# Voltage_Sens.net
KiCad netlist of a schematic drawn in Altium Designer
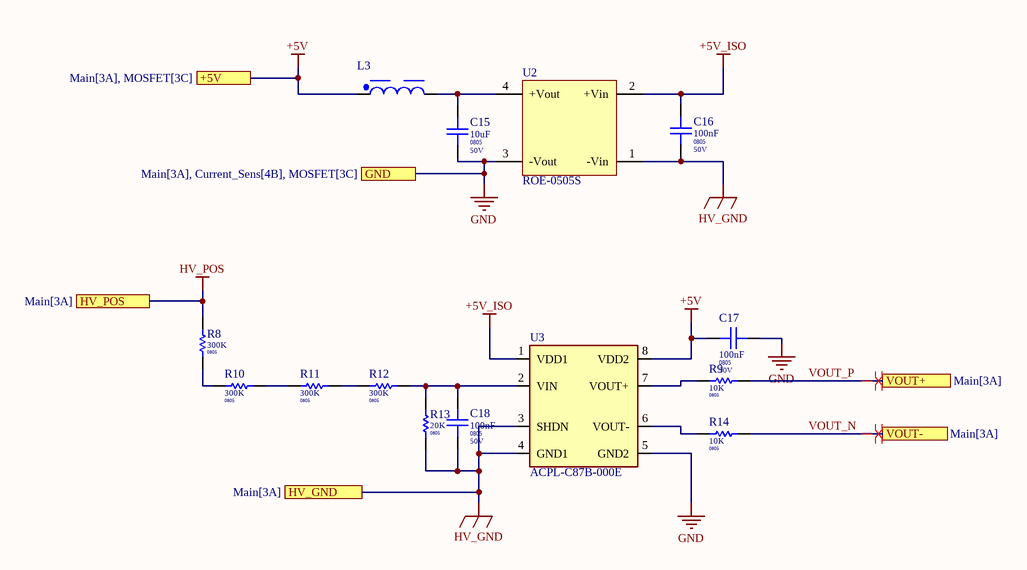
[diagram p0: Voltage_Sens.SchDoc]

(export (version "E")
  (design (tool "Eeschema 10.0.6"))
  (components
    (comp (ref "C15")
      (value "10uF")
      (footprint "CAPC 0805")
      (description "Capacitor Ceramic 10uF 50V 0805")
      (fields
        (field (name "TOLERANCE") "%10")
        (field (name "PACKAGE / CASE") "0805")
        (field (name "VOLTAGE") "50V")
        (field (name "PART NUMBER") "CAPC0588")
      )
      (libsource (lib "Aesk Database Library") (part "NPCapacitor"))
    )
    (comp (ref "C16")
      (value "100nF")
      (footprint "CAPC 0805")
      (description "Capacitor Ceramic 100nF 50V 0805")
      (fields
        (field (name "TOLERANCE") "%10")
        (field (name "PACKAGE / CASE") "0805")
        (field (name "VOLTAGE") "50V")
        (field (name "PART NUMBER") "CAPC0572")
      )
      (libsource (lib "Aesk Database Library") (part "NPCapacitor"))
    )
    (comp (ref "C17")
      (value "100nF")
      (footprint "CAPC 0805")
      (description "Capacitor Ceramic 100nF 50V 0805")
      (fields
        (field (name "TOLERANCE") "%10")
        (field (name "PACKAGE / CASE") "0805")
        (field (name "VOLTAGE") "50V")
        (field (name "PART NUMBER") "CAPC0572")
      )
      (libsource (lib "Aesk Database Library") (part "NPCapacitor"))
    )
    (comp (ref "C18")
      (value "100nF")
      (footprint "CAPC 0805")
      (description "Capacitor Ceramic 100nF 50V 0805")
      (fields
        (field (name "TOLERANCE") "%10")
        (field (name "PACKAGE / CASE") "0805")
        (field (name "VOLTAGE") "50V")
        (field (name "PART NUMBER") "CAPC0572")
      )
      (libsource (lib "Aesk Database Library") (part "NPCapacitor"))
    )
    (comp (ref "L3")
      (value "22uH, 0.66A")
      (footprint "WE-LQFS_3818")
      (description "WE-LQFS SMT Power Inductor, size 3818, 22uH, 0.66A, 481mOhm")
      (fields
        (field (name "MANUFACTURER PART NUMBER") "74406032220")
        (field (name "MANUFACTURER") "Wurth Elektronik")
      )
      (libsource (lib "WE - Passive Components") (part "Inductor - 2"))
    )
    (comp (ref "R8")
      (value "300K")
      (footprint "RESC 0805")
      (description "300K 0805")
      (fields
        (field (name "TOLERANCE") "%5")
        (field (name "POWER") "1/10W")
        (field (name "PACKAGE / CASE") "0805")
      )
      (libsource (lib "Aesk Database Library") (part "Resistor"))
    )
    (comp (ref "R9")
      (value "10K")
      (footprint "RESC 0805")
      (description "10K 0805")
      (fields
        (field (name "TOLERANCE") "%5")
        (field (name "POWER") "1/10W")
        (field (name "PACKAGE / CASE") "0805")
      )
      (libsource (lib "Aesk Database Library") (part "Resistor"))
    )
    (comp (ref "R10")
      (value "300K")
      (footprint "RESC 0805")
      (description "300K 0805")
      (fields
        (field (name "TOLERANCE") "%5")
        (field (name "POWER") "1/10W")
        (field (name "PACKAGE / CASE") "0805")
      )
      (libsource (lib "Aesk Database Library") (part "Resistor"))
    )
    (comp (ref "R11")
      (value "300K")
      (footprint "RESC 0805")
      (description "300K 0805")
      (fields
        (field (name "TOLERANCE") "%5")
        (field (name "POWER") "1/10W")
        (field (name "PACKAGE / CASE") "0805")
      )
      (libsource (lib "Aesk Database Library") (part "Resistor"))
    )
    (comp (ref "R12")
      (value "300K")
      (footprint "RESC 0805")
      (description "300K 0805")
      (fields
        (field (name "TOLERANCE") "%5")
        (field (name "POWER") "1/10W")
        (field (name "PACKAGE / CASE") "0805")
      )
      (libsource (lib "Aesk Database Library") (part "Resistor"))
    )
    (comp (ref "R13")
      (value "20K")
      (footprint "RESC 0805")
      (description "20K 0805")
      (fields
        (field (name "TOLERANCE") "%5")
        (field (name "POWER") "1/10W")
        (field (name "PACKAGE / CASE") "0805")
      )
      (libsource (lib "Aesk Database Library") (part "Resistor"))
    )
    (comp (ref "R14")
      (value "10K")
      (footprint "RESC 0805")
      (description "10K 0805")
      (fields
        (field (name "TOLERANCE") "%5")
        (field (name "POWER") "1/10W")
        (field (name "PACKAGE / CASE") "0805")
      )
      (libsource (lib "Aesk Database Library") (part "Resistor"))
    )
    (comp (ref "U2")
      (value "ROE-0505S")
      (footprint "CONV_ROE-0505S")
      (description "DC DC CONVERTER 5V 1W")
      (libsource (lib "Schlib1") (part "ROE-0505S"))
    )
    (comp (ref "U3")
      (value "ACPL-C87B-000E")
      (footprint "SOIC127P1150X320-8N")
      (description "Isolation Amplifier 1 Circuit Differential 8-SO")
      (fields (field (name "MF") "Broadcom Limited"))
      (libsource (lib "Schlib1") (part "ACPL-C87B-000E"))
    )
  )
  (nets
    (net (code "1") (name "+5V") (class "Default")
      (node (ref "C17") (pin "2") (pinfunction "2_2") (pintype "passive"))
      (node (ref "L3") (pin "1") (pinfunction "1_1") (pintype "passive"))
      (node (ref "U3") (pin "8") (pinfunction "VDD2_8") (pintype "passive"))
    )
    (net (code "2") (name "+5V_ISO") (class "Default")
      (node (ref "C16") (pin "2") (pinfunction "2_2") (pintype "passive"))
      (node (ref "U2") (pin "2") (pinfunction "+Vin_2") (pintype "passive"))
      (node (ref "U3") (pin "1") (pinfunction "VDD1_1") (pintype "passive"))
    )
    (net (code "3") (name "/VOUT_N") (class "Default")
      (node (ref "R14") (pin "2") (pinfunction "2_2") (pintype "passive"))
    )
    (net (code "4") (name "/VOUT_P") (class "Default")
      (node (ref "R9") (pin "2") (pinfunction "2_2") (pintype "passive"))
    )
    (net (code "5") (name "GND") (class "Default")
      (node (ref "C15") (pin "1") (pinfunction "1_1") (pintype "passive"))
      (node (ref "C17") (pin "1") (pinfunction "1_1") (pintype "passive"))
      (node (ref "U2") (pin "3") (pinfunction "-Vout_3") (pintype "passive"))
      (node (ref "U3") (pin "5") (pinfunction "GND2_5") (pintype "passive"))
    )
    (net (code "6") (name "HV_GND") (class "Default")
      (node (ref "C16") (pin "1") (pinfunction "1_1") (pintype "passive"))
      (node (ref "C18") (pin "1") (pinfunction "1_1") (pintype "passive"))
      (node (ref "R13") (pin "1") (pinfunction "1_1") (pintype "passive"))
      (node (ref "U2") (pin "1") (pinfunction "-Vin_1") (pintype "passive"))
      (node (ref "U3") (pin "3") (pinfunction "SHDN_3") (pintype "passive"))
      (node (ref "U3") (pin "4") (pinfunction "GND1_4") (pintype "power_in"))
    )
    (net (code "7") (name "HV_POS") (class "Default")
      (node (ref "R8") (pin "2") (pinfunction "2_2") (pintype "passive"))
    )
    (net (code "8") (name "Net-(R10-Pad1)") (class "Default")
      (node (ref "R10") (pin "1") (pinfunction "1_1") (pintype "passive"))
      (node (ref "R11") (pin "2") (pinfunction "2_2") (pintype "passive"))
    )
    (net (code "9") (name "Net-(R10-Pad2)") (class "Default")
      (node (ref "R10") (pin "2") (pinfunction "2_2") (pintype "passive"))
      (node (ref "R8") (pin "1") (pinfunction "1_1") (pintype "passive"))
    )
    (net (code "10") (name "Net-(R11-Pad1)") (class "Default")
      (node (ref "R11") (pin "1") (pinfunction "1_1") (pintype "passive"))
      (node (ref "R12") (pin "2") (pinfunction "2_2") (pintype "passive"))
    )
    (net (code "11") (name "Net-(U2-+Vout)") (class "Default")
      (node (ref "C15") (pin "2") (pinfunction "2_2") (pintype "passive"))
      (node (ref "L3") (pin "2") (pinfunction "2_2") (pintype "passive"))
      (node (ref "U2") (pin "4") (pinfunction "+Vout_4") (pintype "passive"))
    )
    (net (code "12") (name "Net-(U3-VIN)") (class "Default")
      (node (ref "C18") (pin "2") (pinfunction "2_2") (pintype "passive"))
      (node (ref "R12") (pin "1") (pinfunction "1_1") (pintype "passive"))
      (node (ref "R13") (pin "2") (pinfunction "2_2") (pintype "passive"))
      (node (ref "U3") (pin "2") (pinfunction "VIN_2") (pintype "passive"))
    )
    (net (code "13") (name "Net-(U3-VOUT+)") (class "Default")
      (node (ref "R9") (pin "1") (pinfunction "1_1") (pintype "passive"))
      (node (ref "U3") (pin "7") (pinfunction "VOUT+_7") (pintype "passive"))
    )
    (net (code "14") (name "Net-(U3-VOUT-)") (class "Default")
      (node (ref "R14") (pin "1") (pinfunction "1_1") (pintype "passive"))
      (node (ref "U3") (pin "6") (pinfunction "VOUT-_6") (pintype "passive"))
    )
  )
)
